# powerSupply.net
KiCad netlist of a schematic drawn in Altium Designer
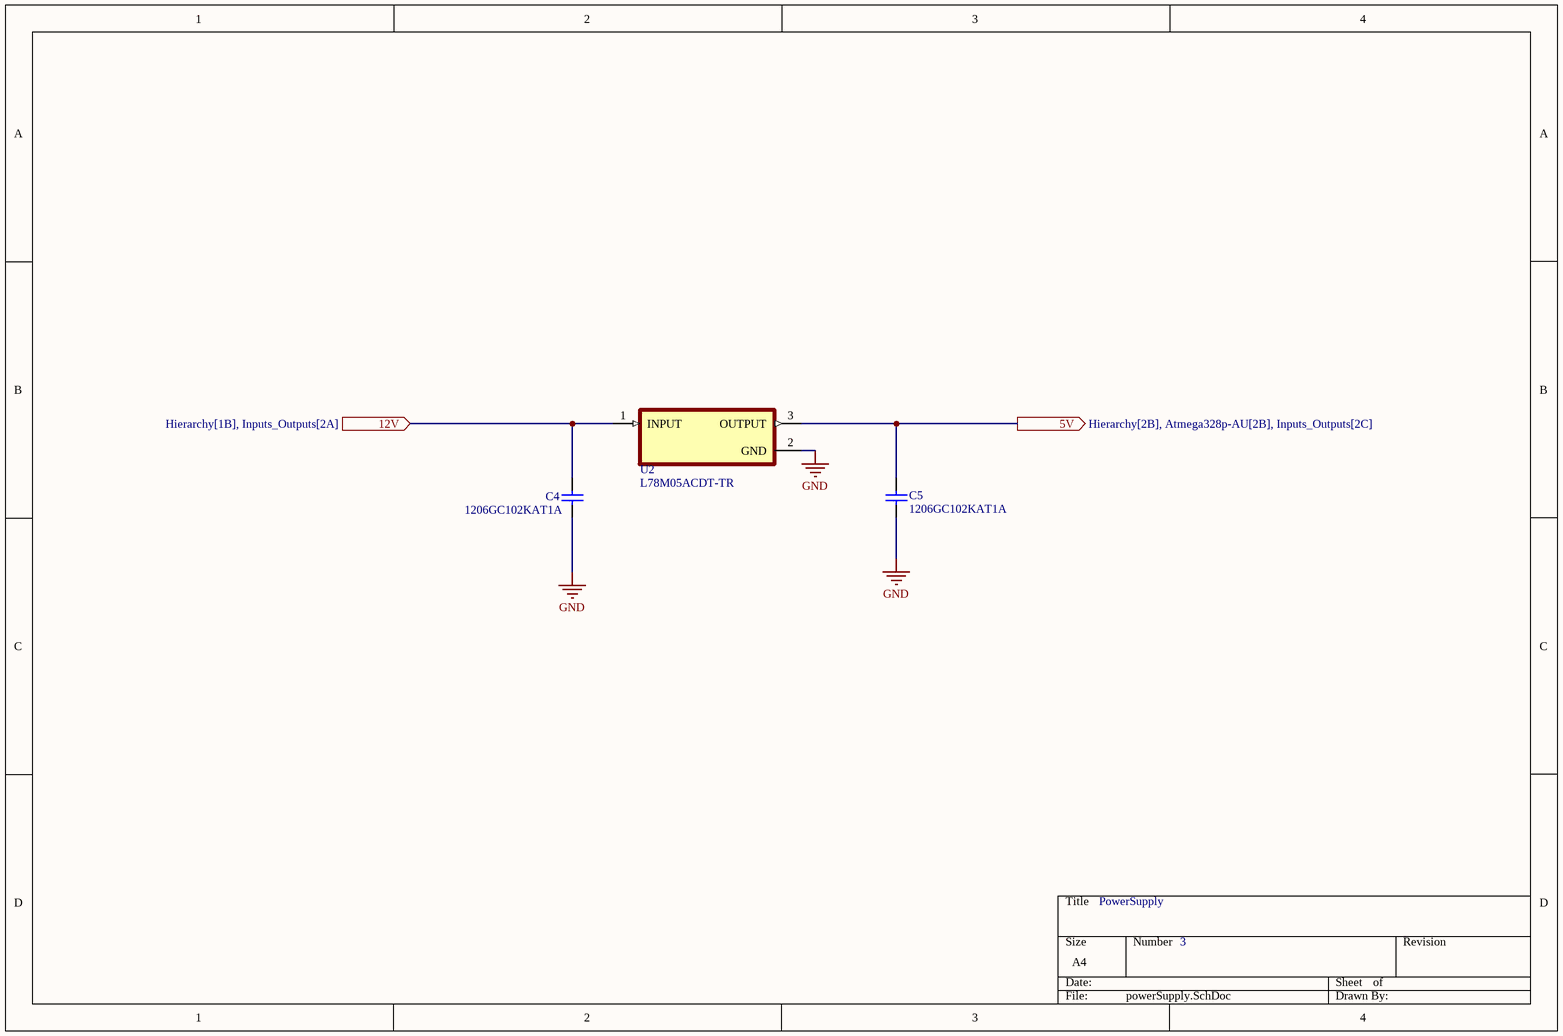
[diagram p0: powerSupply.SchDoc]

(export (version "E")
  (design (tool "Eeschema 10.0.6"))
  (components
    (comp (ref "C4")
      (value "1206GC102KAT1A")
      (footprint "AVX-1206-2_L")
      (description "Chip Capacitor, 1 nF, +/- 10%, -55 to 125 degC, 1206 (3216 Metric), RoHS, Tape and Reel")
      (fields (field (name "TOLERANCE") "10%") (field (name "MANUFACTURER") "AVX"))
      (libsource (lib "Altium Content Vault") (part "CAP-NP-2"))
    )
    (comp (ref "C5")
      (value "1206GC102KAT1A")
      (footprint "AVX-1206-2_L")
      (description "Chip Capacitor, 1 nF, +/- 10%, -55 to 125 degC, 1206 (3216 Metric), RoHS, Tape and Reel")
      (fields (field (name "TOLERANCE") "10%") (field (name "MANUFACTURER") "AVX"))
      (libsource (lib "Altium Content Vault") (part "CAP-NP-2"))
    )
    (comp (ref "U2")
      (value "L78M05ACDT-TR")
      (footprint "DPAK228P972X240-4N")
      (description "Linear Voltage Regulator IC 1 Output 500mA DPAK")
      (fields (field (name "MF") "STMicroelectronics"))
      (libsource (lib "L78M05ACDT-TR") (part "L78M05ACDT-TR"))
    )
  )
  (nets
    (net (code "1") (name "/5V") (class "Default")
      (node (ref "C5") (pin "1") (pinfunction "1_1") (pintype "passive"))
      (node (ref "U2") (pin "3") (pinfunction "OUTPUT_3") (pintype "output"))
    )
    (net (code "2") (name "/12V") (class "Default")
      (node (ref "C4") (pin "2") (pinfunction "2_2") (pintype "passive"))
      (node (ref "U2") (pin "1") (pinfunction "INPUT_1") (pintype "input"))
    )
    (net (code "3") (name "GND") (class "Default")
      (node (ref "C4") (pin "1") (pinfunction "1_1") (pintype "passive"))
      (node (ref "C5") (pin "2") (pinfunction "2_2") (pintype "passive"))
      (node (ref "U2") (pin "2") (pinfunction "GND_2") (pintype "power_in"))
    )
  )
)
